# Adafruit_GUVA_UV_Sensor_Breakout.net
KiCad netlist of a schematic drawn in EAGLE
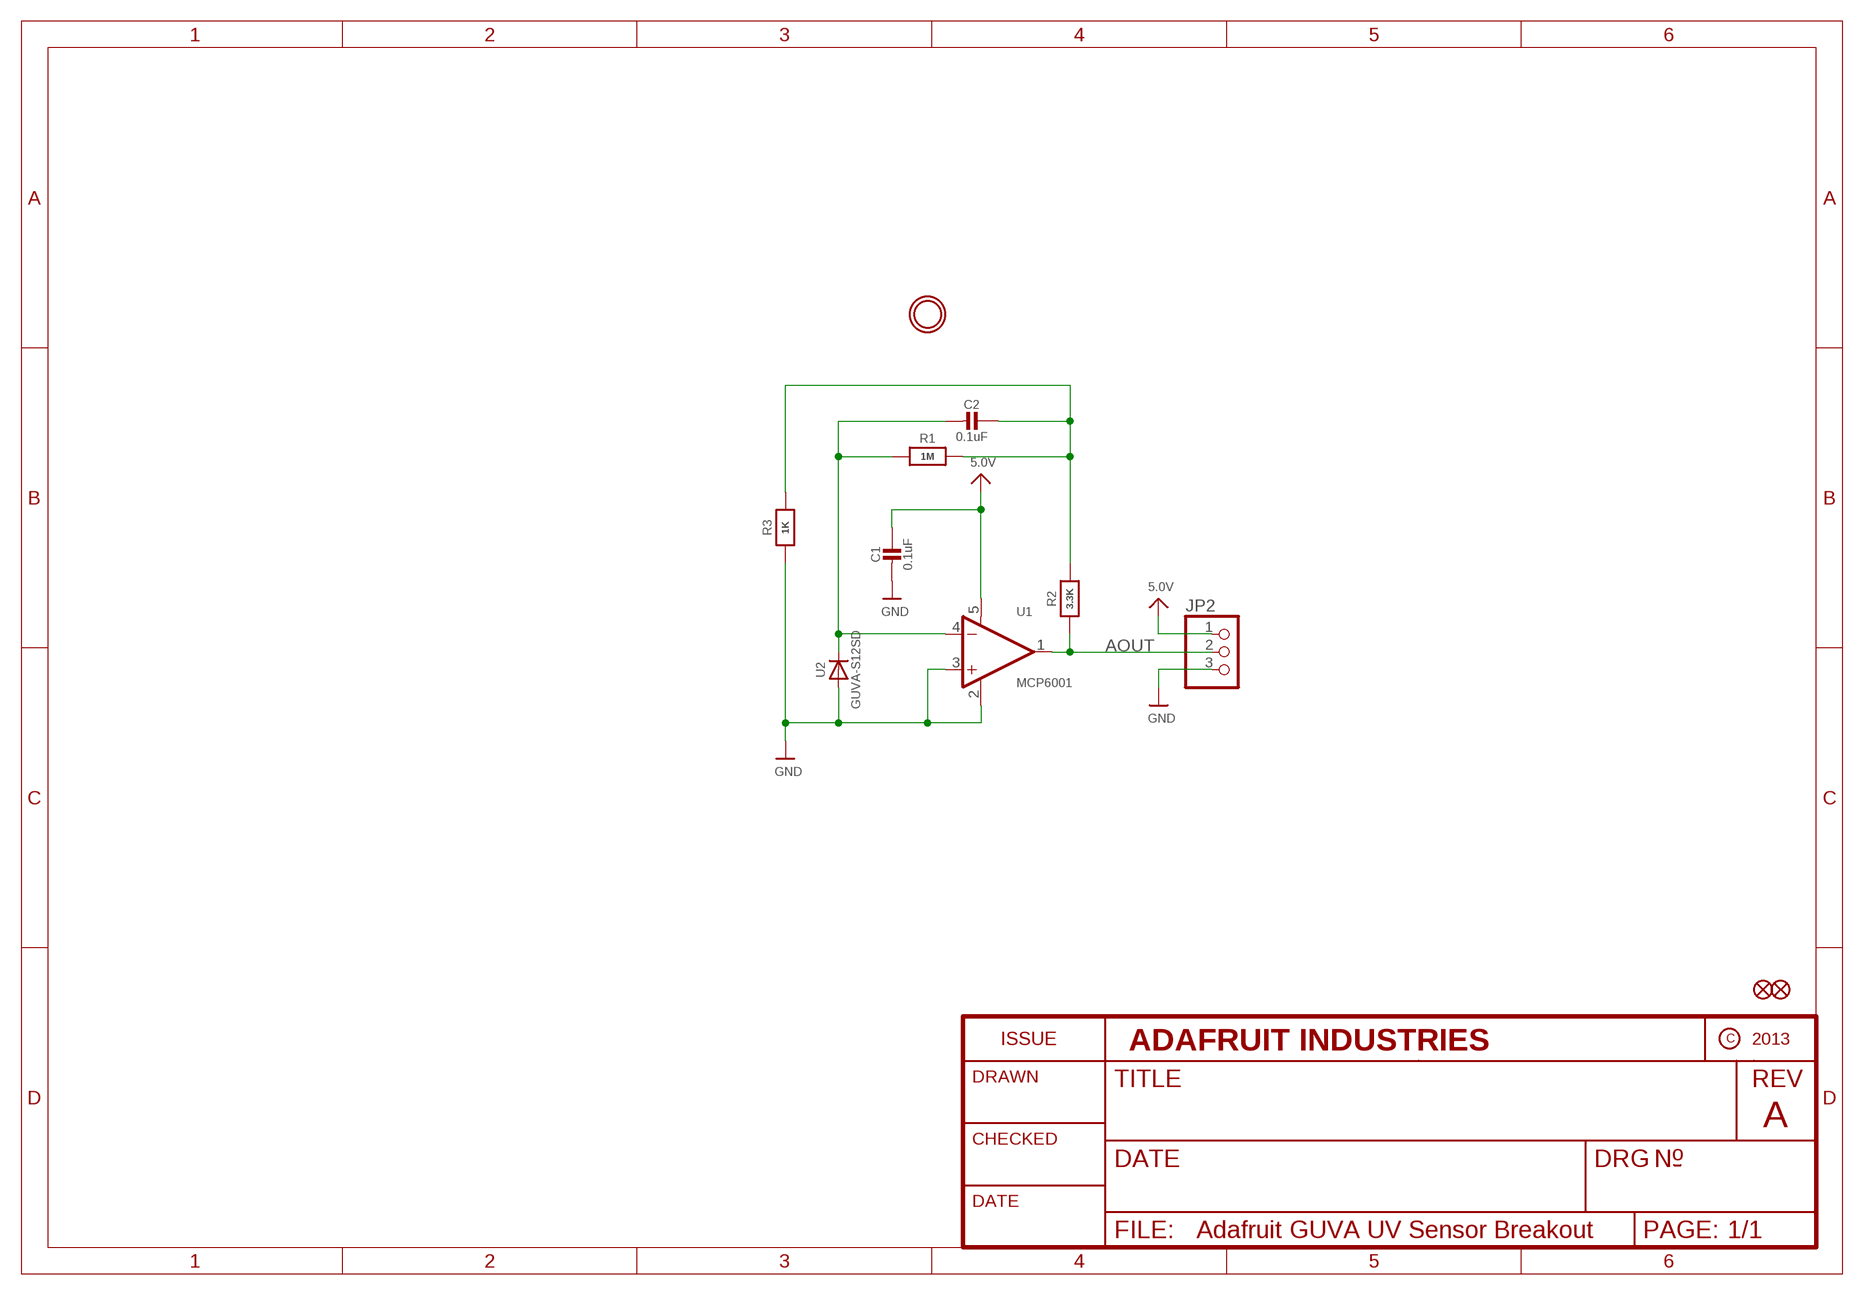
[diagram p0: schematic, sheet 1]

(export (version "E")
  (design (tool "Eeschema 10.0.6"))
  (components
    (comp (ref "C1")
      (value "0.1uF")
      (footprint "eagle-import:0805-NO")
      (libsource (lib "eagle-import") (part "CAP_CERAMIC0805-NOOUTLINE"))
    )
    (comp (ref "C2")
      (value "0.1uF")
      (footprint "eagle-import:0805-NO")
      (libsource (lib "eagle-import") (part "CAP_CERAMIC0805-NOOUTLINE"))
    )
    (comp (ref "FID1")
      (value "FIDUCIAL\"\"")
      (footprint "eagle-import:FIDUCIAL_1MM")
      (libsource (lib "eagle-import") (part "FIDUCIAL{dblquote}{dblquote}"))
    )
    (comp (ref "FID2")
      (value "FIDUCIAL\"\"")
      (footprint "eagle-import:FIDUCIAL_1MM")
      (libsource (lib "eagle-import") (part "FIDUCIAL{dblquote}{dblquote}"))
    )
    (comp (ref "JP2")
      (value "PINHD-1X3CB")
      (footprint "eagle-import:1X03-CLEANBIG")
      (libsource (lib "eagle-import") (part "PINHD-1X3CB"))
    )
    (comp (ref "R1")
      (value "1M")
      (footprint "eagle-import:0805-NO")
      (libsource (lib "eagle-import") (part "RESISTOR0805_NOOUTLINE"))
    )
    (comp (ref "R2")
      (value "3.3K")
      (footprint "eagle-import:0805-NO")
      (libsource (lib "eagle-import") (part "RESISTOR0805_NOOUTLINE"))
    )
    (comp (ref "R3")
      (value "1K")
      (footprint "eagle-import:0805-NO")
      (libsource (lib "eagle-import") (part "RESISTOR0805_NOOUTLINE"))
    )
    (comp (ref "U$6")
      (value "MOUNTINGHOLE2.5")
      (footprint "eagle-import:MOUNTINGHOLE_2.5_PLATED")
      (libsource (lib "eagle-import") (part "MOUNTINGHOLE2.5"))
    )
    (comp (ref "U1")
      (value "MCP6001")
      (footprint "eagle-import:SOT23-5")
      (libsource (lib "eagle-import") (part "OPAMP_SINGLESOT235"))
    )
    (comp (ref "U2")
      (value "GUVA-S12SD")
      (footprint "eagle-import:GUVA-S12SD")
      (libsource (lib "eagle-import") (part "UV_GUVA-S12SD"))
    )
  )
  (nets
    (net (code "1") (name "/AOUT") (class "Default")
      (node (ref "JP2") (pin "2") (pinfunction "2_2") (pintype "passive"))
      (node (ref "R2") (pin "1") (pinfunction "1_1") (pintype "passive"))
      (node (ref "U1") (pin "1") (pinfunction "OUT_1") (pintype "output"))
    )
    (net (code "2") (name "5.0V") (class "Default")
      (node (ref "C1") (pin "1") (pinfunction "1_1") (pintype "passive"))
      (node (ref "JP2") (pin "1") (pinfunction "1_1") (pintype "passive"))
      (node (ref "U1") (pin "5") (pinfunction "V+_5") (pintype "power_in"))
    )
    (net (code "3") (name "GND") (class "Default")
      (node (ref "C1") (pin "2") (pinfunction "2_2") (pintype "passive"))
      (node (ref "JP2") (pin "3") (pinfunction "3_3") (pintype "passive"))
      (node (ref "R3") (pin "1") (pinfunction "1_1") (pintype "passive"))
      (node (ref "U1") (pin "2") (pinfunction "V-_2") (pintype "power_in"))
      (node (ref "U1") (pin "3") (pinfunction "+IN_3") (pintype "input"))
      (node (ref "U2") (pin "A") (pinfunction "A_A") (pintype "passive"))
    )
    (net (code "4") (name "Net-(C2-Pad1)") (class "Default")
      (node (ref "C2") (pin "1") (pinfunction "1_1") (pintype "passive"))
      (node (ref "R1") (pin "2") (pinfunction "2_2") (pintype "passive"))
      (node (ref "R2") (pin "2") (pinfunction "2_2") (pintype "passive"))
      (node (ref "R3") (pin "2") (pinfunction "2_2") (pintype "passive"))
    )
    (net (code "5") (name "Net-(U1--IN)") (class "Default")
      (node (ref "C2") (pin "2") (pinfunction "2_2") (pintype "passive"))
      (node (ref "R1") (pin "1") (pinfunction "1_1") (pintype "passive"))
      (node (ref "U1") (pin "4") (pinfunction "-IN_4") (pintype "input"))
      (node (ref "U2") (pin "K") (pinfunction "C_K") (pintype "passive"))
    )
  )
)
